# bean.net
KiCad netlist of a schematic drawn in EAGLE
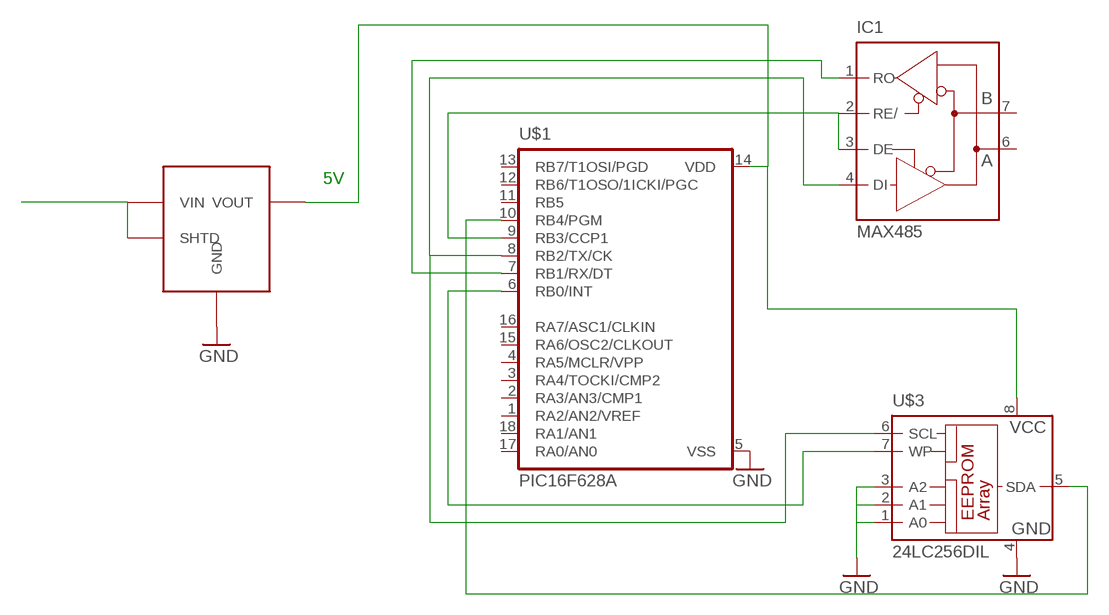
[diagram p0: schematic, sheet 1]

(export (version "E")
  (design (tool "Eeschema 10.0.6"))
  (components
    (comp (ref "IC1")
      (value "MAX485")
      (footprint "eagle-import:DIL08")
      (fields (field (name "MPN") "MAX481CPA+"))
      (libsource (lib "eagle-import") (part "MAX485"))
    )
    (comp (ref "U$1")
      (value "PIC16F628A")
      (footprint "eagle-import:DIL18")
      (libsource (lib "eagle-import") (part "PIC16F628A"))
    )
    (comp (ref "U$2")
      (value "POLOLU-2098")
      (footprint "eagle-import:POLOLU-10-13")
      (libsource (lib "eagle-import") (part "POLOLU-2098"))
    )
    (comp (ref "U$3")
      (value "24LC256DIL")
      (footprint "eagle-import:DIL08")
      (libsource (lib "eagle-import") (part "24LC256DIL"))
    )
  )
  (nets
    (net (code "1") (name "GND") (class "Default")
      (node (ref "U$1") (pin "5") (pinfunction "VSS_5") (pintype "power_in"))
      (node (ref "U$2") (pin "P$3") (pinfunction "GND_P$3") (pintype "bidirectional"))
      (node (ref "U$3") (pin "1") (pinfunction "A0_1") (pintype "input"))
      (node (ref "U$3") (pin "2") (pinfunction "A1_2") (pintype "input"))
      (node (ref "U$3") (pin "3") (pinfunction "A2_3") (pintype "input"))
      (node (ref "U$3") (pin "4") (pinfunction "GND_4") (pintype "power_in"))
    )
    (net (code "2") (name "Net-(IC1A-DE)") (class "Default")
      (node (ref "IC1") (pin "2") (pinfunction "RE/_2") (pintype "input"))
      (node (ref "IC1") (pin "3") (pinfunction "DE_3") (pintype "input"))
      (node (ref "U$1") (pin "9") (pinfunction "RB3/CCP1_9") (pintype "bidirectional"))
    )
    (net (code "3") (name "Net-(IC1A-DI)") (class "Default")
      (node (ref "IC1") (pin "4") (pinfunction "DI_4") (pintype "input"))
      (node (ref "U$1") (pin "8") (pinfunction "RB2/TX/CK_8") (pintype "bidirectional"))
      (node (ref "U$3") (pin "6") (pinfunction "SCL_6") (pintype "input"))
    )
    (net (code "4") (name "Net-(IC1A-RO)") (class "Default")
      (node (ref "IC1") (pin "1") (pinfunction "RO_1") (pintype "output"))
      (node (ref "U$1") (pin "7") (pinfunction "RB1/RX/DT_7") (pintype "bidirectional"))
    )
    (net (code "5") (name "Net-(U$1-RB0{slash}INT)") (class "Default")
      (node (ref "U$1") (pin "6") (pinfunction "RB0/INT_6") (pintype "bidirectional"))
      (node (ref "U$3") (pin "7") (pinfunction "WP_7") (pintype "input"))
    )
    (net (code "6") (name "Net-(U$1-RB4{slash}PGM)") (class "Default")
      (node (ref "U$1") (pin "10") (pinfunction "RB4/PGM_10") (pintype "bidirectional"))
      (node (ref "U$3") (pin "5") (pinfunction "SDA_5") (pintype "bidirectional"))
    )
    (net (code "7") (name "Net-(U$1-VDD)") (class "Default")
      (node (ref "U$1") (pin "14") (pinfunction "VDD_14") (pintype "power_in"))
      (node (ref "U$2") (pin "P$4") (pinfunction "VOUT_P$4") (pintype "bidirectional"))
      (node (ref "U$3") (pin "8") (pinfunction "VCC_8") (pintype "power_in"))
    )
    (net (code "8") (name "Net-(U$2-SHTD)") (class "Default")
      (node (ref "U$2") (pin "P$1") (pinfunction "SHTD_P$1") (pintype "power_in"))
      (node (ref "U$2") (pin "P$2") (pinfunction "VIN_P$2") (pintype "power_in"))
    )
    (net (code "9") (name "unconnected-(IC1A-A-Pad6)") (class "Default")
      (node (ref "IC1") (pin "6") (pinfunction "A_6") (pintype "passive"))
    )
    (net (code "10") (name "unconnected-(IC1A-B-Pad7)") (class "Default")
      (node (ref "IC1") (pin "7") (pinfunction "B_7") (pintype "passive"))
    )
    (net (code "11") (name "unconnected-(U$1-RA0{slash}AN0-Pad17)") (class "Default")
      (node (ref "U$1") (pin "17") (pinfunction "RA0/AN0_17") (pintype "bidirectional"))
    )
    (net (code "12") (name "unconnected-(U$1-RA1{slash}AN1-Pad18)") (class "Default")
      (node (ref "U$1") (pin "18") (pinfunction "RA1/AN1_18") (pintype "bidirectional"))
    )
    (net (code "13") (name "unconnected-(U$1-RA2{slash}AN2{slash}VREF-Pad1)") (class "Default")
      (node (ref "U$1") (pin "1") (pinfunction "RA2/AN2/VREF_1") (pintype "bidirectional"))
    )
    (net (code "14") (name "unconnected-(U$1-RA3{slash}AN3{slash}CMP1-Pad2)") (class "Default")
      (node (ref "U$1") (pin "2") (pinfunction "RA3/AN3/CMP1_2") (pintype "bidirectional"))
    )
    (net (code "15") (name "unconnected-(U$1-RA4{slash}TOCKI{slash}CMP2-Pad3)") (class "Default")
      (node (ref "U$1") (pin "3") (pinfunction "RA4/TOCKI/CMP2_3") (pintype "bidirectional"))
    )
    (net (code "16") (name "unconnected-(U$1-RA5{slash}MCLR{slash}VPP-Pad4)") (class "Default")
      (node (ref "U$1") (pin "4") (pinfunction "RA5/MCLR/VPP_4") (pintype "input"))
    )
    (net (code "17") (name "unconnected-(U$1-RA6{slash}OSC2{slash}CLKOUT-Pad15)") (class "Default")
      (node (ref "U$1") (pin "15") (pinfunction "RA6/OSC2/CLKOUT_15") (pintype "bidirectional"))
    )
    (net (code "18") (name "unconnected-(U$1-RA7{slash}ASC1{slash}CLKIN-Pad16)") (class "Default")
      (node (ref "U$1") (pin "16") (pinfunction "RA7/ASC1/CLKIN_16") (pintype "bidirectional"))
    )
    (net (code "19") (name "unconnected-(U$1-RB5-Pad11)") (class "Default")
      (node (ref "U$1") (pin "11") (pinfunction "RB5_11") (pintype "bidirectional"))
    )
    (net (code "20") (name "unconnected-(U$1-RB6{slash}T1OSO{slash}1ICKI{slash}PGC-Pad12)") (class "Default")
      (node (ref "U$1") (pin "12") (pinfunction "RB6/T1OSO/1ICKI/PGC_12") (pintype "bidirectional"))
    )
    (net (code "21") (name "unconnected-(U$1-RB7{slash}T1OSI{slash}PGD-Pad13)") (class "Default")
      (node (ref "U$1") (pin "13") (pinfunction "RB7/T1OSI/PGD_13") (pintype "bidirectional"))
    )
  )
)
